# Ethernet.net
KiCad netlist of a schematic drawn in Altium Designer
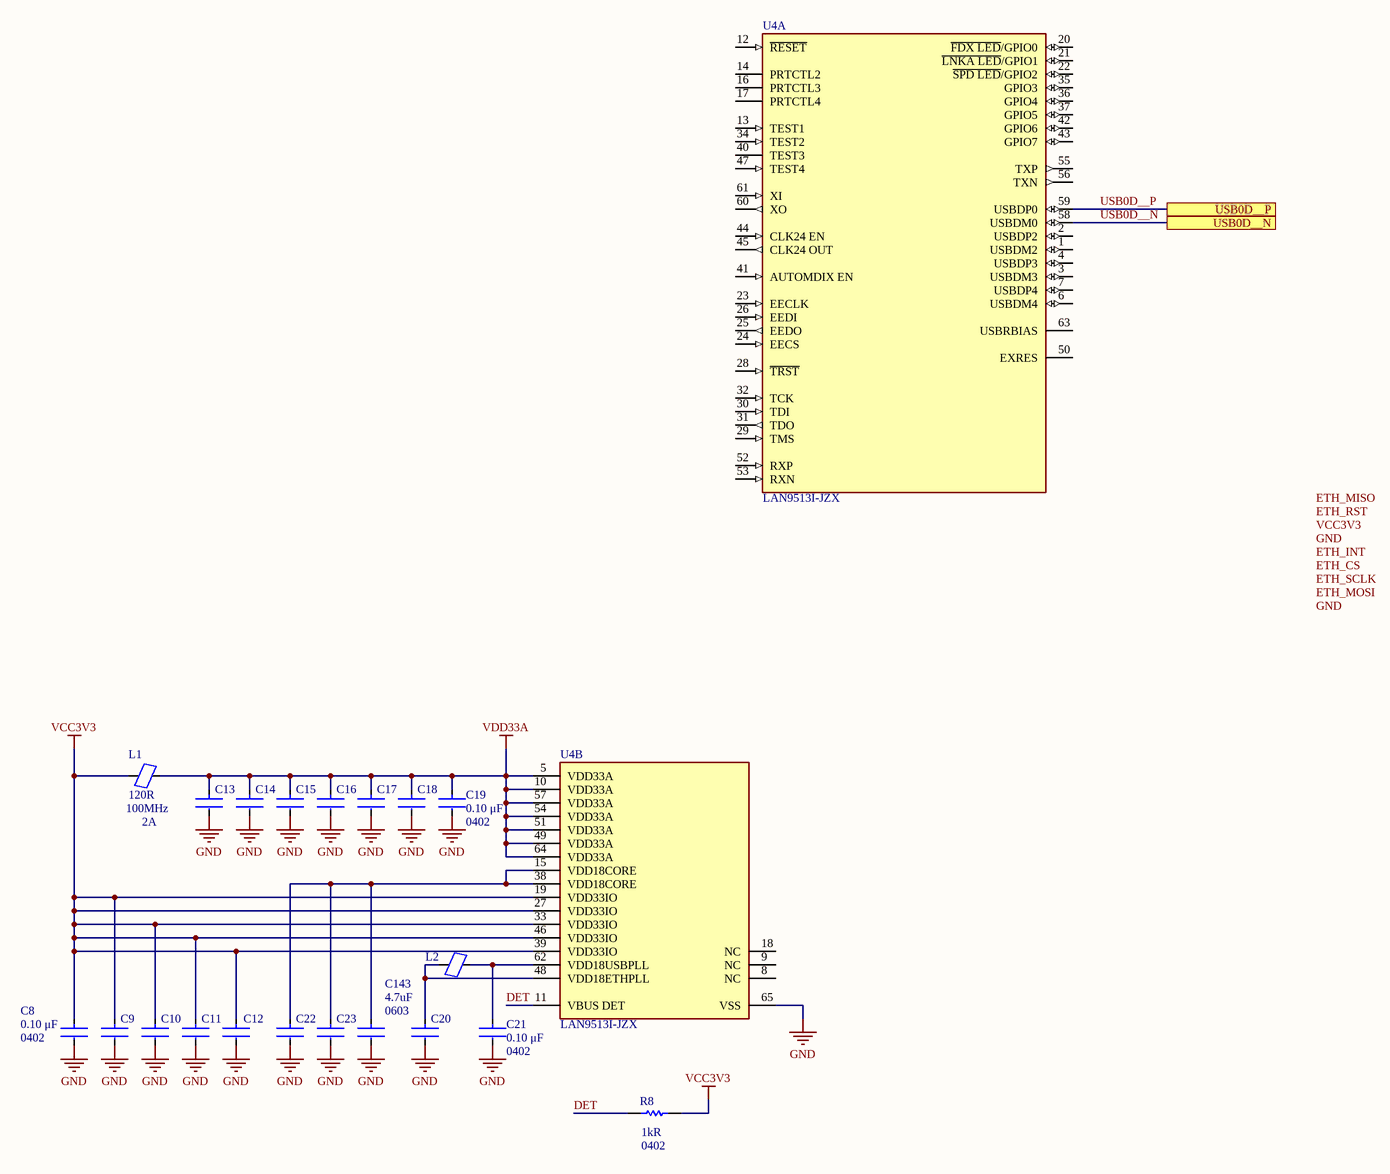
[diagram p0: Ethernet.SchDoc]

(export (version "E")
  (design (tool "Eeschema 10.0.6"))
  (components
    (comp (ref "C8")
      (value "C0402C104K8PACTU")
      (footprint "FP-C0402-BB-MFG")
      (description "CAP CER 0.1UF 10V X5R 0402")
      (fields
        (field (name "CAPACITANCE") "0.10 μF")
        (field (name "MANUFACTURER") "Kemet")
        (field (name "TOLERANCE") "0.1")
        (field (name "CASE/PACKAGE") "0402")
      )
      (libsource (lib "Altium Content Vault") (part "b4654b650e69147ec39a6b967a45e02"))
    )
    (comp (ref "C9")
      (value "C0402C104K8PACTU")
      (footprint "FP-C0402-BB-MFG")
      (description "CAP CER 0.1UF 10V X5R 0402")
      (fields (field (name "MANUFACTURER") "Kemet") (field (name "TOLERANCE") "0.1"))
      (libsource (lib "Altium Content Vault") (part "b4654b650e69147ec39a6b967a45e02"))
    )
    (comp (ref "C10")
      (value "C0402C104K8PACTU")
      (footprint "FP-C0402-BB-MFG")
      (description "CAP CER 0.1UF 10V X5R 0402")
      (fields (field (name "MANUFACTURER") "Kemet") (field (name "TOLERANCE") "0.1"))
      (libsource (lib "Altium Content Vault") (part "b4654b650e69147ec39a6b967a45e02"))
    )
    (comp (ref "C11")
      (value "C0402C104K8PACTU")
      (footprint "FP-C0402-BB-MFG")
      (description "CAP CER 0.1UF 10V X5R 0402")
      (fields (field (name "MANUFACTURER") "Kemet") (field (name "TOLERANCE") "0.1"))
      (libsource (lib "Altium Content Vault") (part "b4654b650e69147ec39a6b967a45e02"))
    )
    (comp (ref "C12")
      (value "C0402C104K8PACTU")
      (footprint "FP-C0402-BB-MFG")
      (description "CAP CER 0.1UF 10V X5R 0402")
      (fields (field (name "MANUFACTURER") "Kemet") (field (name "TOLERANCE") "0.1"))
      (libsource (lib "Altium Content Vault") (part "b4654b650e69147ec39a6b967a45e02"))
    )
    (comp (ref "C13")
      (value "C0402C104K8PACTU")
      (footprint "FP-C0402-BB-MFG")
      (description "CAP CER 0.1UF 10V X5R 0402")
      (fields (field (name "MANUFACTURER") "Kemet") (field (name "TOLERANCE") "0.1"))
      (libsource (lib "Altium Content Vault") (part "b4654b650e69147ec39a6b967a45e02"))
    )
    (comp (ref "C14")
      (value "C0402C104K8PACTU")
      (footprint "FP-C0402-BB-MFG")
      (description "CAP CER 0.1UF 10V X5R 0402")
      (fields (field (name "MANUFACTURER") "Kemet") (field (name "TOLERANCE") "0.1"))
      (libsource (lib "Altium Content Vault") (part "b4654b650e69147ec39a6b967a45e02"))
    )
    (comp (ref "C15")
      (value "C0402C104K8PACTU")
      (footprint "FP-C0402-BB-MFG")
      (description "CAP CER 0.1UF 10V X5R 0402")
      (fields (field (name "MANUFACTURER") "Kemet") (field (name "TOLERANCE") "0.1"))
      (libsource (lib "Altium Content Vault") (part "b4654b650e69147ec39a6b967a45e02"))
    )
    (comp (ref "C16")
      (value "C0402C104K8PACTU")
      (footprint "FP-C0402-BB-MFG")
      (description "CAP CER 0.1UF 10V X5R 0402")
      (fields (field (name "MANUFACTURER") "Kemet") (field (name "TOLERANCE") "0.1"))
      (libsource (lib "Altium Content Vault") (part "b4654b650e69147ec39a6b967a45e02"))
    )
    (comp (ref "C17")
      (value "C0402C104K8PACTU")
      (footprint "FP-C0402-BB-MFG")
      (description "CAP CER 0.1UF 10V X5R 0402")
      (fields (field (name "MANUFACTURER") "Kemet") (field (name "TOLERANCE") "0.1"))
      (libsource (lib "Altium Content Vault") (part "b4654b650e69147ec39a6b967a45e02"))
    )
    (comp (ref "C18")
      (value "C0402C104K8PACTU")
      (footprint "FP-C0402-BB-MFG")
      (description "CAP CER 0.1UF 10V X5R 0402")
      (fields (field (name "MANUFACTURER") "Kemet") (field (name "TOLERANCE") "0.1"))
      (libsource (lib "Altium Content Vault") (part "b4654b650e69147ec39a6b967a45e02"))
    )
    (comp (ref "C19")
      (value "0.10 μF")
      (footprint "FP-C0402-BB-MFG")
      (description "CAP CER 0.1UF 10V X5R 0402")
      (fields
        (field (name "MANUFACTURER") "Kemet")
        (field (name "TOLERANCE") "0.1")
        (field (name "CASE CODE (IMPERIAL)") "0402")
      )
      (libsource (lib "Altium Content Vault") (part "b4654b650e69147ec39a6b967a45e02"))
    )
    (comp (ref "C20")
      (value "C0402C104K8PACTU")
      (footprint "FP-C0402-BB-MFG")
      (description "CAP CER 0.1UF 10V X5R 0402")
      (fields (field (name "MANUFACTURER") "Kemet") (field (name "TOLERANCE") "0.1"))
      (libsource (lib "Altium Content Vault") (part "b4654b650e69147ec39a6b967a45e02"))
    )
    (comp (ref "C21")
      (value "0.10 μF")
      (footprint "FP-C0402-BB-MFG")
      (description "CAP CER 0.1UF 10V X5R 0402")
      (fields
        (field (name "MANUFACTURER") "Kemet")
        (field (name "TOLERANCE") "0.1")
        (field (name "CASE CODE (IMPERIAL)") "0402")
      )
      (libsource (lib "Altium Content Vault") (part "b4654b650e69147ec39a6b967a45e02"))
    )
    (comp (ref "C22")
      (value "C0402C104K8PACTU")
      (footprint "FP-C0402-BB-MFG")
      (description "CAP CER 0.1UF 10V X5R 0402")
      (fields (field (name "MANUFACTURER") "Kemet") (field (name "TOLERANCE") "0.1"))
      (libsource (lib "Altium Content Vault") (part "b4654b650e69147ec39a6b967a45e02"))
    )
    (comp (ref "C23")
      (value "C0402C104K8PACTU")
      (footprint "FP-C0402-BB-MFG")
      (description "CAP CER 0.1UF 10V X5R 0402")
      (fields (field (name "MANUFACTURER") "Kemet") (field (name "TOLERANCE") "0.1"))
      (libsource (lib "Altium Content Vault") (part "b4654b650e69147ec39a6b967a45e02"))
    )
    (comp (ref "C143")
      (value "4.7uF")
      (footprint "FP-C0603-CG-MFG")
      (description "CAP CER 4.7UF 6.3V X5R 0603")
      (fields
        (field (name "TOLERANCE") "10%")
        (field (name "MANUFACTURER") "Kemet")
        (field (name "CASE/PACKAGE") "0603")
      )
      (libsource (lib "Altium Content Vault") (part "11868f565c42a9108669ba33697ecf6"))
    )
    (comp (ref "L1")
      (value "FB_120@100MHz")
      (footprint "CAP0402i")
      (description "Ferrite Beads Multi-Layer 120Ohm 25% 100MHz 2A 0.055Ohm DCR 0402 T/R")
      (fields
        (field (name "TOLERANCE") "25%")
        (field (name "IMPEDANCE") "120R")
        (field (name "MAX DC CURRENT") "2A")
        (field (name "TEST FREQUENCY") "100MHz")
        (field (name "PART NUMBER") "BLM15PX121SN1D")
      )
      (libsource (lib "AmpherLib") (part "Ferrite Bead_ 0402_120R_100MHz_2A"))
    )
    (comp (ref "L2")
      (value "FB_120@100MHz")
      (footprint "CAP0402i")
      (description "Ferrite Beads Multi-Layer 120Ohm 25% 100MHz 2A 0.055Ohm DCR 0402 T/R")
      (fields (field (name "TOLERANCE") "25%") (field (name "PART NUMBER") "BLM15PX121SN1D"))
      (libsource (lib "AmpherLib") (part "Ferrite Bead_ 0402_120R_100MHz_2A"))
    )
    (comp (ref "R8")
      (value "1kR")
      (footprint "RESC1005X40X25NL05T05")
      (description "Chip Resistor, 1 KOhm, +/- 1%, 100 mW, -55 to 155 degC, 0402 (1005 Metric), RoHS, Tape and Reel")
      (fields
        (field (name "PARTNUMBER") "ERJ-2RKF1001X")
        (field (name "MANUFACTURER") "Basic Passives")
        (field (name "CAS~{E}/PACKAGE") "0402")
      )
      (libsource (lib "Altium Content Vault") (part "RES-2"))
    )
    (comp (ref "U4")
      (value "LAN9513I-JZX")
      (footprint "FP-LAN9513I-JZX-MFG")
      (description "IC USB 2.0 ETHER CTRLR 64QFN")
      (libsource (lib "Altium Content Vault") (part "5c5afc2b2c57bf8600ed866ab6e4262"))
    )
  )
  (nets
    (net (code "1") (name "/DET") (class "Default")
      (node (ref "R8") (pin "1") (pinfunction "1_1") (pintype "passive"))
      (node (ref "U4") (pin "11") (pinfunction "VBUS_DET_11") (pintype "power_in"))
    )
    (net (code "8") (name "/USB0D__N") (class "Default")
      (node (ref "U4") (pin "58") (pinfunction "USBDM0_58") (pintype "bidirectional"))
    )
    (net (code "9") (name "/USB0D__P") (class "Default")
      (node (ref "U4") (pin "59") (pinfunction "USBDP0_59") (pintype "bidirectional"))
    )
    (net (code "10") (name "GND") (class "Default")
      (node (ref "C10") (pin "2") (pinfunction "2_2") (pintype "passive"))
      (node (ref "C11") (pin "2") (pinfunction "2_2") (pintype "passive"))
      (node (ref "C12") (pin "2") (pinfunction "2_2") (pintype "passive"))
      (node (ref "C13") (pin "2") (pinfunction "2_2") (pintype "passive"))
      (node (ref "C14") (pin "2") (pinfunction "2_2") (pintype "passive"))
      (node (ref "C143") (pin "2") (pinfunction "2_2") (pintype "passive"))
      (node (ref "C15") (pin "2") (pinfunction "2_2") (pintype "passive"))
      (node (ref "C16") (pin "2") (pinfunction "2_2") (pintype "passive"))
      (node (ref "C17") (pin "2") (pinfunction "2_2") (pintype "passive"))
      (node (ref "C18") (pin "2") (pinfunction "2_2") (pintype "passive"))
      (node (ref "C19") (pin "2") (pinfunction "2_2") (pintype "passive"))
      (node (ref "C20") (pin "2") (pinfunction "2_2") (pintype "passive"))
      (node (ref "C21") (pin "2") (pinfunction "2_2") (pintype "passive"))
      (node (ref "C22") (pin "2") (pinfunction "2_2") (pintype "passive"))
      (node (ref "C23") (pin "2") (pinfunction "2_2") (pintype "passive"))
      (node (ref "C8") (pin "2") (pinfunction "2_2") (pintype "passive"))
      (node (ref "C9") (pin "2") (pinfunction "2_2") (pintype "passive"))
      (node (ref "U4") (pin "65") (pinfunction "VSS_65") (pintype "power_in"))
    )
    (net (code "11") (name "Net-(C143-Pad1)") (class "Default")
      (node (ref "C143") (pin "1") (pinfunction "1_1") (pintype "passive"))
      (node (ref "C22") (pin "1") (pinfunction "1_1") (pintype "passive"))
      (node (ref "C23") (pin "1") (pinfunction "1_1") (pintype "passive"))
      (node (ref "U4") (pin "15") (pinfunction "VDD18CORE_15") (pintype "power_in"))
      (node (ref "U4") (pin "38") (pinfunction "VDD18CORE_38") (pintype "power_in"))
    )
    (net (code "12") (name "Net-(U4B-VDD18ETHPLL)") (class "Default")
      (node (ref "C20") (pin "1") (pinfunction "1_1") (pintype "passive"))
      (node (ref "L2") (pin "1") (pinfunction "1_1") (pintype "passive"))
      (node (ref "U4") (pin "48") (pinfunction "VDD18ETHPLL_48") (pintype "power_in"))
    )
    (net (code "13") (name "Net-(U4B-VDD18USBPLL)") (class "Default")
      (node (ref "C21") (pin "1") (pinfunction "1_1") (pintype "passive"))
      (node (ref "L2") (pin "2") (pinfunction "2_2") (pintype "passive"))
      (node (ref "U4") (pin "62") (pinfunction "VDD18USBPLL_62") (pintype "power_in"))
    )
    (net (code "14") (name "VCC3V3") (class "Default")
      (node (ref "C10") (pin "1") (pinfunction "1_1") (pintype "passive"))
      (node (ref "C11") (pin "1") (pinfunction "1_1") (pintype "passive"))
      (node (ref "C12") (pin "1") (pinfunction "1_1") (pintype "passive"))
      (node (ref "C8") (pin "1") (pinfunction "1_1") (pintype "passive"))
      (node (ref "C9") (pin "1") (pinfunction "1_1") (pintype "passive"))
      (node (ref "L1") (pin "1") (pinfunction "1_1") (pintype "passive"))
      (node (ref "R8") (pin "2") (pinfunction "2_2") (pintype "passive"))
      (node (ref "U4") (pin "19") (pinfunction "VDD33IO_19") (pintype "power_in"))
      (node (ref "U4") (pin "27") (pinfunction "VDD33IO_27") (pintype "power_in"))
      (node (ref "U4") (pin "33") (pinfunction "VDD33IO_33") (pintype "power_in"))
      (node (ref "U4") (pin "39") (pinfunction "VDD33IO_39") (pintype "power_in"))
      (node (ref "U4") (pin "46") (pinfunction "VDD33IO_46") (pintype "power_in"))
    )
    (net (code "15") (name "VDD33A") (class "Default")
      (node (ref "C13") (pin "1") (pinfunction "1_1") (pintype "passive"))
      (node (ref "C14") (pin "1") (pinfunction "1_1") (pintype "passive"))
      (node (ref "C15") (pin "1") (pinfunction "1_1") (pintype "passive"))
      (node (ref "C16") (pin "1") (pinfunction "1_1") (pintype "passive"))
      (node (ref "C17") (pin "1") (pinfunction "1_1") (pintype "passive"))
      (node (ref "C18") (pin "1") (pinfunction "1_1") (pintype "passive"))
      (node (ref "C19") (pin "1") (pinfunction "1_1") (pintype "passive"))
      (node (ref "L1") (pin "2") (pinfunction "2_2") (pintype "passive"))
      (node (ref "U4") (pin "10") (pinfunction "VDD33A_10") (pintype "power_in"))
      (node (ref "U4") (pin "49") (pinfunction "VDD33A_49") (pintype "power_in"))
      (node (ref "U4") (pin "5") (pinfunction "VDD33A_5") (pintype "power_in"))
      (node (ref "U4") (pin "51") (pinfunction "VDD33A_51") (pintype "power_in"))
      (node (ref "U4") (pin "54") (pinfunction "VDD33A_54") (pintype "power_in"))
      (node (ref "U4") (pin "57") (pinfunction "VDD33A_57") (pintype "power_in"))
      (node (ref "U4") (pin "64") (pinfunction "VDD33A_64") (pintype "power_in"))
    )
    (net (code "16") (name "unconnected-(U4A-AUTOMDIX_EN-Pad41)") (class "Default")
      (node (ref "U4") (pin "41") (pinfunction "AUTOMDIX_EN_41") (pintype "input"))
    )
    (net (code "17") (name "unconnected-(U4A-CLK24_EN-Pad44)") (class "Default")
      (node (ref "U4") (pin "44") (pinfunction "CLK24_EN_44") (pintype "input"))
    )
    (net (code "18") (name "unconnected-(U4A-CLK24_OUT-Pad45)") (class "Default")
      (node (ref "U4") (pin "45") (pinfunction "CLK24_OUT_45") (pintype "output"))
    )
    (net (code "19") (name "unconnected-(U4A-EECLK-Pad23)") (class "Default")
      (node (ref "U4") (pin "23") (pinfunction "EECLK_23") (pintype "input"))
    )
    (net (code "20") (name "unconnected-(U4A-EECS-Pad24)") (class "Default")
      (node (ref "U4") (pin "24") (pinfunction "EECS_24") (pintype "input"))
    )
    (net (code "21") (name "unconnected-(U4A-EEDI-Pad26)") (class "Default")
      (node (ref "U4") (pin "26") (pinfunction "EEDI_26") (pintype "input"))
    )
    (net (code "22") (name "unconnected-(U4A-EEDO-Pad25)") (class "Default")
      (node (ref "U4") (pin "25") (pinfunction "EEDO_25") (pintype "output"))
    )
    (net (code "23") (name "unconnected-(U4A-EXRES-Pad50)") (class "Default")
      (node (ref "U4") (pin "50") (pinfunction "EXRES_50") (pintype "passive"))
    )
    (net (code "24") (name "unconnected-(U4A-GPIO3-Pad35)") (class "Default")
      (node (ref "U4") (pin "35") (pinfunction "GPIO3_35") (pintype "bidirectional"))
    )
    (net (code "25") (name "unconnected-(U4A-GPIO4-Pad36)") (class "Default")
      (node (ref "U4") (pin "36") (pinfunction "GPIO4_36") (pintype "bidirectional"))
    )
    (net (code "26") (name "unconnected-(U4A-GPIO5-Pad37)") (class "Default")
      (node (ref "U4") (pin "37") (pinfunction "GPIO5_37") (pintype "bidirectional"))
    )
    (net (code "27") (name "unconnected-(U4A-GPIO6-Pad42)") (class "Default")
      (node (ref "U4") (pin "42") (pinfunction "GPIO6_42") (pintype "bidirectional"))
    )
    (net (code "28") (name "unconnected-(U4A-GPIO7-Pad43)") (class "Default")
      (node (ref "U4") (pin "43") (pinfunction "GPIO7_43") (pintype "bidirectional"))
    )
    (net (code "29") (name "unconnected-(U4A-PRTCTL2-Pad14)") (class "Default")
      (node (ref "U4") (pin "14") (pinfunction "PRTCTL2_14") (pintype "passive"))
    )
    (net (code "30") (name "unconnected-(U4A-PRTCTL3-Pad16)") (class "Default")
      (node (ref "U4") (pin "16") (pinfunction "PRTCTL3_16") (pintype "passive"))
    )
    (net (code "31") (name "unconnected-(U4A-PRTCTL4-Pad17)") (class "Default")
      (node (ref "U4") (pin "17") (pinfunction "PRTCTL4_17") (pintype "passive"))
    )
    (net (code "32") (name "unconnected-(U4A-RXN-Pad53)") (class "Default")
      (node (ref "U4") (pin "53") (pinfunction "RXN_53") (pintype "input"))
    )
    (net (code "33") (name "unconnected-(U4A-RXP-Pad52)") (class "Default")
      (node (ref "U4") (pin "52") (pinfunction "RXP_52") (pintype "input"))
    )
    (net (code "34") (name "unconnected-(U4A-TCK-Pad32)") (class "Default")
      (node (ref "U4") (pin "32") (pinfunction "TCK_32") (pintype "input"))
    )
    (net (code "35") (name "unconnected-(U4A-TDI-Pad30)") (class "Default")
      (node (ref "U4") (pin "30") (pinfunction "TDI_30") (pintype "input"))
    )
    (net (code "36") (name "unconnected-(U4A-TDO-Pad31)") (class "Default")
      (node (ref "U4") (pin "31") (pinfunction "TDO_31") (pintype "output"))
    )
    (net (code "37") (name "unconnected-(U4A-TEST1-Pad13)") (class "Default")
      (node (ref "U4") (pin "13") (pinfunction "TEST1_13") (pintype "input"))
    )
    (net (code "38") (name "unconnected-(U4A-TEST2-Pad34)") (class "Default")
      (node (ref "U4") (pin "34") (pinfunction "TEST2_34") (pintype "input"))
    )
    (net (code "39") (name "unconnected-(U4A-TEST3-Pad40)") (class "Default")
      (node (ref "U4") (pin "40") (pinfunction "TEST3_40") (pintype "passive"))
    )
    (net (code "40") (name "unconnected-(U4A-TEST4-Pad47)") (class "Default")
      (node (ref "U4") (pin "47") (pinfunction "TEST4_47") (pintype "input"))
    )
    (net (code "41") (name "unconnected-(U4A-TMS-Pad29)") (class "Default")
      (node (ref "U4") (pin "29") (pinfunction "TMS_29") (pintype "input"))
    )
    (net (code "42") (name "unconnected-(U4A-TXN-Pad56)") (class "Default")
      (node (ref "U4") (pin "56") (pinfunction "TXN_56") (pintype "output"))
    )
    (net (code "43") (name "unconnected-(U4A-TXP-Pad55)") (class "Default")
      (node (ref "U4") (pin "55") (pinfunction "TXP_55") (pintype "output"))
    )
    (net (code "44") (name "unconnected-(U4A-USBDM2-Pad1)") (class "Default")
      (node (ref "U4") (pin "1") (pinfunction "USBDM2_1") (pintype "bidirectional"))
    )
    (net (code "45") (name "unconnected-(U4A-USBDM3-Pad3)") (class "Default")
      (node (ref "U4") (pin "3") (pinfunction "USBDM3_3") (pintype "bidirectional"))
    )
    (net (code "46") (name "unconnected-(U4A-USBDM4-Pad6)") (class "Default")
      (node (ref "U4") (pin "6") (pinfunction "USBDM4_6") (pintype "bidirectional"))
    )
    (net (code "47") (name "unconnected-(U4A-USBDP2-Pad2)") (class "Default")
      (node (ref "U4") (pin "2") (pinfunction "USBDP2_2") (pintype "bidirectional"))
    )
    (net (code "48") (name "unconnected-(U4A-USBDP3-Pad4)") (class "Default")
      (node (ref "U4") (pin "4") (pinfunction "USBDP3_4") (pintype "bidirectional"))
    )
    (net (code "49") (name "unconnected-(U4A-USBDP4-Pad7)") (class "Default")
      (node (ref "U4") (pin "7") (pinfunction "USBDP4_7") (pintype "bidirectional"))
    )
    (net (code "50") (name "unconnected-(U4A-USBRBIAS-Pad63)") (class "Default")
      (node (ref "U4") (pin "63") (pinfunction "USBRBIAS_63") (pintype "passive"))
    )
    (net (code "51") (name "unconnected-(U4A-XI-Pad61)") (class "Default")
      (node (ref "U4") (pin "61") (pinfunction "XI_61") (pintype "input"))
    )
    (net (code "52") (name "unconnected-(U4A-XO-Pad60)") (class "Default")
      (node (ref "U4") (pin "60") (pinfunction "XO_60") (pintype "output"))
    )
    (net (code "53") (name "unconnected-(U4A-~{FDX_LED}{slash}GPIO0-Pad20)") (class "Default")
      (node (ref "U4") (pin "20") (pinfunction "~{FDX_LED}/GPIO0_20") (pintype "bidirectional"))
    )
    (net (code "54") (name "unconnected-(U4A-~{LNKA_LED}{slash}GPIO1-Pad21)") (class "Default")
      (node (ref "U4") (pin "21") (pinfunction "~{LNKA_LED}/GPIO1_21") (pintype "bidirectional"))
    )
    (net (code "55") (name "unconnected-(U4A-~{RESET}-Pad12)") (class "Default")
      (node (ref "U4") (pin "12") (pinfunction "~{RESET}_12") (pintype "input"))
    )
    (net (code "56") (name "unconnected-(U4A-~{SPD_LED}{slash}GPIO2-Pad22)") (class "Default")
      (node (ref "U4") (pin "22") (pinfunction "~{SPD_LED}/GPIO2_22") (pintype "bidirectional"))
    )
    (net (code "57") (name "unconnected-(U4A-~{TRST}-Pad28)") (class "Default")
      (node (ref "U4") (pin "28") (pinfunction "~{TRST}_28") (pintype "input"))
    )
    (net (code "58") (name "unconnected-(U4B-NC-Pad8)") (class "Default")
      (node (ref "U4") (pin "8") (pinfunction "NC_8") (pintype "power_in"))
    )
    (net (code "59") (name "unconnected-(U4B-NC-Pad9)") (class "Default")
      (node (ref "U4") (pin "9") (pinfunction "NC_9") (pintype "power_in"))
    )
    (net (code "60") (name "unconnected-(U4B-NC-Pad18)") (class "Default")
      (node (ref "U4") (pin "18") (pinfunction "NC_18") (pintype "power_in"))
    )
  )
)
